# STM8L_SensorsUnit.net
KiCad netlist of a schematic drawn in EAGLE
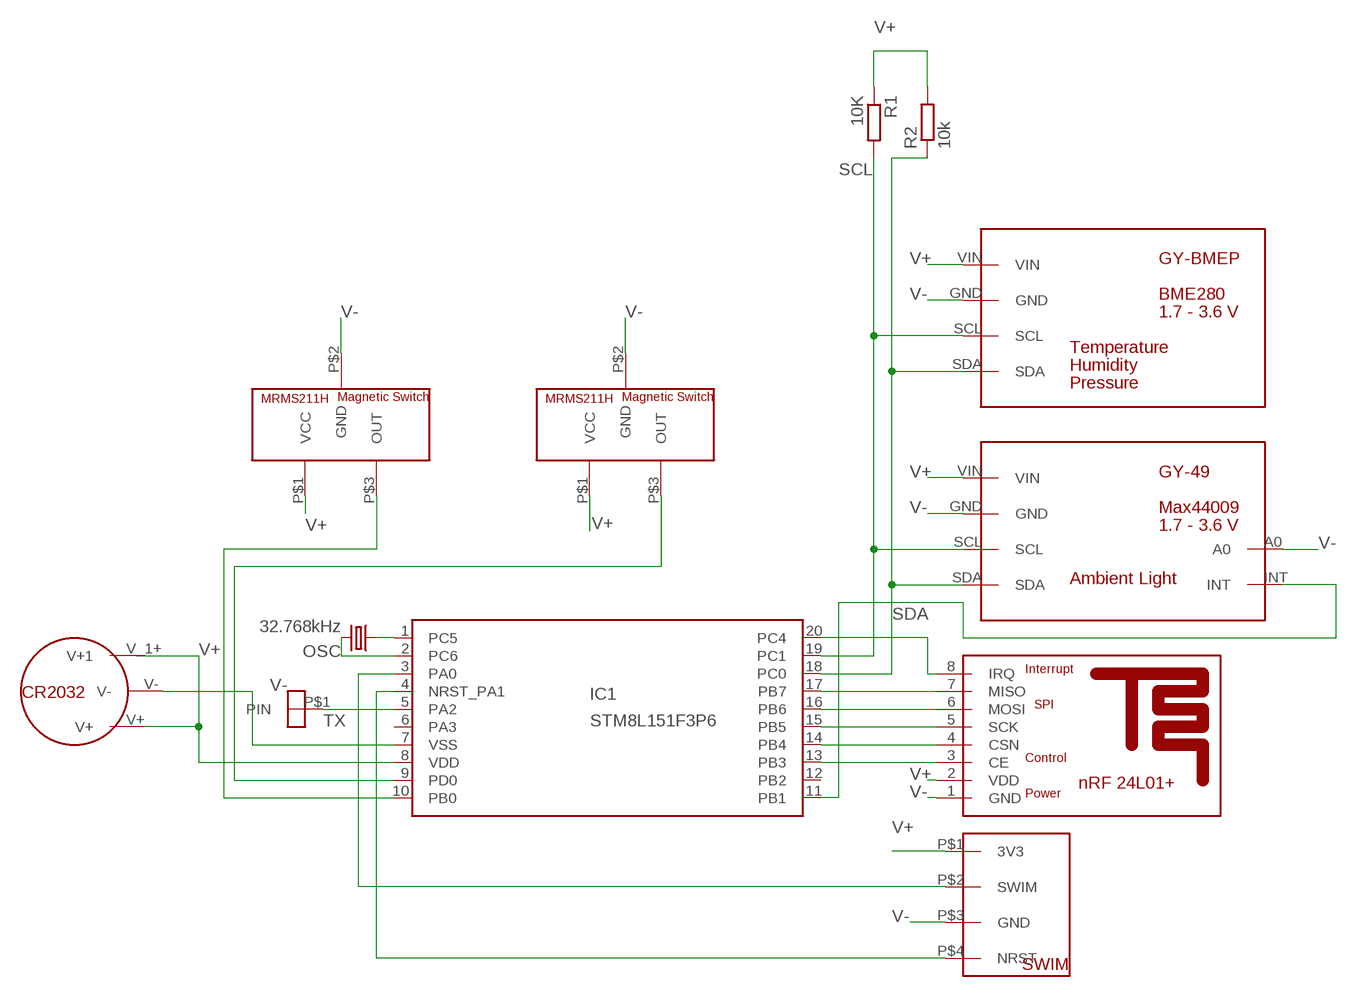
[diagram p0: schematic, sheet 1]

(export (version "E")
  (design (tool "Eeschema 10.0.6"))
  (components
    (comp (ref "IC1")
      (value "STM8L151F3P6")
      (footprint "eagle-import:STM8L151F3P")
      (libsource (lib "eagle-import") (part "STM8L151F3P6"))
    )
    (comp (ref "OSC")
      (value "32.768kHz")
      (footprint "eagle-import:CRYSTAL-SMD-3.2X1.5MM")
      (libsource (lib "eagle-import") (part "CRYSTAL3.2X1.5MM"))
    )
    (comp (ref "R1")
      (value "10K")
      (footprint "eagle-import:M1206")
      (libsource (lib "eagle-import") (part "R-EU_M1206"))
    )
    (comp (ref "R2")
      (value "10k")
      (footprint "eagle-import:M1206")
      (libsource (lib "eagle-import") (part "R-EU_M1206"))
    )
    (comp (ref "U$1")
      (value "NRF24L01+REFDESIGNMINI")
      (footprint "eagle-import:NRF24L01+REFDESIGN-MINI")
      (libsource (lib "eagle-import") (part "NRF24L01+REFDESIGNMINI"))
    )
    (comp (ref "U$2")
      (value "GY-49G-49-SURF")
      (footprint "eagle-import:GY-49-SURF")
      (libsource (lib "eagle-import") (part "GY-49G-49-SURF"))
    )
    (comp (ref "U$3")
      (value "GY-BMEPGY-BMEP-NOHOLE")
      (footprint "eagle-import:GY-BMEP-NOHOLE")
      (libsource (lib "eagle-import") (part "GY-BMEPGY-BMEP-NOHOLE"))
    )
    (comp (ref "U$4")
      (value "MRMS211H-MAGNETIC-SWITCH")
      (footprint "eagle-import:3PIN-MM")
      (libsource (lib "eagle-import") (part "MRMS211H-MAGNETIC-SWITCH"))
    )
    (comp (ref "U$5")
      (value "CR2032-ISOLATED")
      (footprint "eagle-import:CR2032-ISOLATED")
      (libsource (lib "eagle-import") (part "CR2032-ISOLATED"))
    )
    (comp (ref "U$6")
      (value "MRMS211H-MAGNETIC-SWITCH")
      (footprint "eagle-import:3PIN-MM")
      (libsource (lib "eagle-import") (part "MRMS211H-MAGNETIC-SWITCH"))
    )
    (comp (ref "U$7")
      (value "SWIM")
      (footprint "eagle-import:SWIM")
      (libsource (lib "eagle-import") (part "SWIM"))
    )
    (comp (ref "U$8")
      (value "PINSIGNAL")
      (footprint "eagle-import:PIN")
      (libsource (lib "eagle-import") (part "PINSIGNAL"))
    )
  )
  (nets
    (net (code "1") (name "/SCL") (class "Default")
      (node (ref "IC1") (pin "19") (pinfunction "PC1_19") (pintype "bidirectional"))
      (node (ref "R1") (pin "2") (pinfunction "2_2") (pintype "passive"))
      (node (ref "U$2") (pin "SCL") (pinfunction "SCL_SCL") (pintype "bidirectional"))
      (node (ref "U$3") (pin "SCL") (pinfunction "SCL_SCL") (pintype "bidirectional"))
    )
    (net (code "2") (name "/SDA") (class "Default")
      (node (ref "IC1") (pin "18") (pinfunction "PC0_18") (pintype "bidirectional"))
      (node (ref "R2") (pin "1") (pinfunction "1_1") (pintype "passive"))
      (node (ref "U$2") (pin "SDA") (pinfunction "SDA_SDA") (pintype "bidirectional"))
      (node (ref "U$3") (pin "SDA") (pinfunction "SDA_SDA") (pintype "bidirectional"))
    )
    (net (code "3") (name "/TX") (class "Default")
      (node (ref "IC1") (pin "5") (pinfunction "PA2_5") (pintype "bidirectional"))
      (node (ref "U$8") (pin "P$1") (pinfunction "PIN_P$1") (pintype "bidirectional"))
    )
    (net (code "4") (name "/V+") (class "Default")
      (node (ref "IC1") (pin "8") (pinfunction "VDD_8") (pintype "bidirectional"))
      (node (ref "R1") (pin "1") (pinfunction "1_1") (pintype "passive"))
      (node (ref "R2") (pin "2") (pinfunction "2_2") (pintype "passive"))
      (node (ref "U$1") (pin "2") (pinfunction "VDD_2") (pintype "bidirectional"))
      (node (ref "U$2") (pin "VIN") (pinfunction "VIN_VIN") (pintype "bidirectional"))
      (node (ref "U$3") (pin "VIN") (pinfunction "VIN_VIN") (pintype "bidirectional"))
      (node (ref "U$4") (pin "P$1") (pinfunction "VCC_P$1") (pintype "bidirectional"))
      (node (ref "U$5") (pin "V+") (pinfunction "V+_V+") (pintype "bidirectional"))
      (node (ref "U$5") (pin "V_1+") (pinfunction "V+1_V_1+") (pintype "bidirectional"))
      (node (ref "U$6") (pin "P$1") (pinfunction "VCC_P$1") (pintype "bidirectional"))
      (node (ref "U$7") (pin "P$1") (pinfunction "3V3_P$1") (pintype "bidirectional"))
    )
    (net (code "5") (name "/V-") (class "Default")
      (node (ref "IC1") (pin "7") (pinfunction "VSS_7") (pintype "bidirectional"))
      (node (ref "U$1") (pin "1") (pinfunction "GND_1") (pintype "bidirectional"))
      (node (ref "U$2") (pin "A0") (pinfunction "A0_A0") (pintype "bidirectional"))
      (node (ref "U$2") (pin "GND") (pinfunction "GND_GND") (pintype "bidirectional"))
      (node (ref "U$3") (pin "GND") (pinfunction "GND_GND") (pintype "bidirectional"))
      (node (ref "U$4") (pin "P$2") (pinfunction "GND_P$2") (pintype "bidirectional"))
      (node (ref "U$5") (pin "V-") (pinfunction "V-_V-") (pintype "bidirectional"))
      (node (ref "U$6") (pin "P$2") (pinfunction "GND_P$2") (pintype "bidirectional"))
      (node (ref "U$7") (pin "P$3") (pinfunction "GND_P$3") (pintype "bidirectional"))
    )
    (net (code "6") (name "Net-(IC1-NRST_PA1)") (class "Default")
      (node (ref "IC1") (pin "4") (pinfunction "NRST_PA1_4") (pintype "bidirectional"))
      (node (ref "U$7") (pin "P$4") (pinfunction "NRST_P$4") (pintype "bidirectional"))
    )
    (net (code "7") (name "Net-(IC1-PA0)") (class "Default")
      (node (ref "IC1") (pin "3") (pinfunction "PA0_3") (pintype "bidirectional"))
      (node (ref "U$7") (pin "P$2") (pinfunction "SWIM_P$2") (pintype "bidirectional"))
    )
    (net (code "8") (name "Net-(IC1-PB0)") (class "Default")
      (node (ref "IC1") (pin "10") (pinfunction "PB0_10") (pintype "bidirectional"))
      (node (ref "U$6") (pin "P$3") (pinfunction "OUT_P$3") (pintype "bidirectional"))
    )
    (net (code "9") (name "Net-(IC1-PB1)") (class "Default")
      (node (ref "IC1") (pin "11") (pinfunction "PB1_11") (pintype "bidirectional"))
      (node (ref "U$2") (pin "INT") (pinfunction "INT_INT") (pintype "bidirectional"))
    )
    (net (code "10") (name "Net-(IC1-PB3)") (class "Default")
      (node (ref "IC1") (pin "13") (pinfunction "PB3_13") (pintype "bidirectional"))
      (node (ref "U$1") (pin "3") (pinfunction "CE_3") (pintype "bidirectional"))
    )
    (net (code "11") (name "Net-(IC1-PB4)") (class "Default")
      (node (ref "IC1") (pin "14") (pinfunction "PB4_14") (pintype "bidirectional"))
      (node (ref "U$1") (pin "4") (pinfunction "CSN_4") (pintype "bidirectional"))
    )
    (net (code "12") (name "Net-(IC1-PB5)") (class "Default")
      (node (ref "IC1") (pin "15") (pinfunction "PB5_15") (pintype "bidirectional"))
      (node (ref "U$1") (pin "5") (pinfunction "SCK_5") (pintype "bidirectional"))
    )
    (net (code "13") (name "Net-(IC1-PB6)") (class "Default")
      (node (ref "IC1") (pin "16") (pinfunction "PB6_16") (pintype "bidirectional"))
      (node (ref "U$1") (pin "6") (pinfunction "MOSI_6") (pintype "bidirectional"))
    )
    (net (code "14") (name "Net-(IC1-PB7)") (class "Default")
      (node (ref "IC1") (pin "17") (pinfunction "PB7_17") (pintype "bidirectional"))
      (node (ref "U$1") (pin "7") (pinfunction "MISO_7") (pintype "bidirectional"))
    )
    (net (code "15") (name "Net-(IC1-PC4)") (class "Default")
      (node (ref "IC1") (pin "20") (pinfunction "PC4_20") (pintype "bidirectional"))
      (node (ref "U$1") (pin "8") (pinfunction "IRQ_8") (pintype "bidirectional"))
    )
    (net (code "16") (name "Net-(IC1-PC5)") (class "Default")
      (node (ref "IC1") (pin "1") (pinfunction "PC5_1") (pintype "bidirectional"))
      (node (ref "OSC") (pin "P$1") (pinfunction "1_P$1") (pintype "passive"))
    )
    (net (code "17") (name "Net-(IC1-PC6)") (class "Default")
      (node (ref "IC1") (pin "2") (pinfunction "PC6_2") (pintype "bidirectional"))
      (node (ref "OSC") (pin "P$2") (pinfunction "2_P$2") (pintype "passive"))
    )
    (net (code "18") (name "Net-(IC1-PD0)") (class "Default")
      (node (ref "IC1") (pin "9") (pinfunction "PD0_9") (pintype "bidirectional"))
      (node (ref "U$4") (pin "P$3") (pinfunction "OUT_P$3") (pintype "bidirectional"))
    )
    (net (code "19") (name "unconnected-(IC1-PA3-Pad6)") (class "Default")
      (node (ref "IC1") (pin "6") (pinfunction "PA3_6") (pintype "bidirectional"))
    )
    (net (code "20") (name "unconnected-(IC1-PB2-Pad12)") (class "Default")
      (node (ref "IC1") (pin "12") (pinfunction "PB2_12") (pintype "bidirectional"))
    )
  )
)
